# Etcha_Sketch.net
KiCad netlist of a schematic drawn in EAGLE
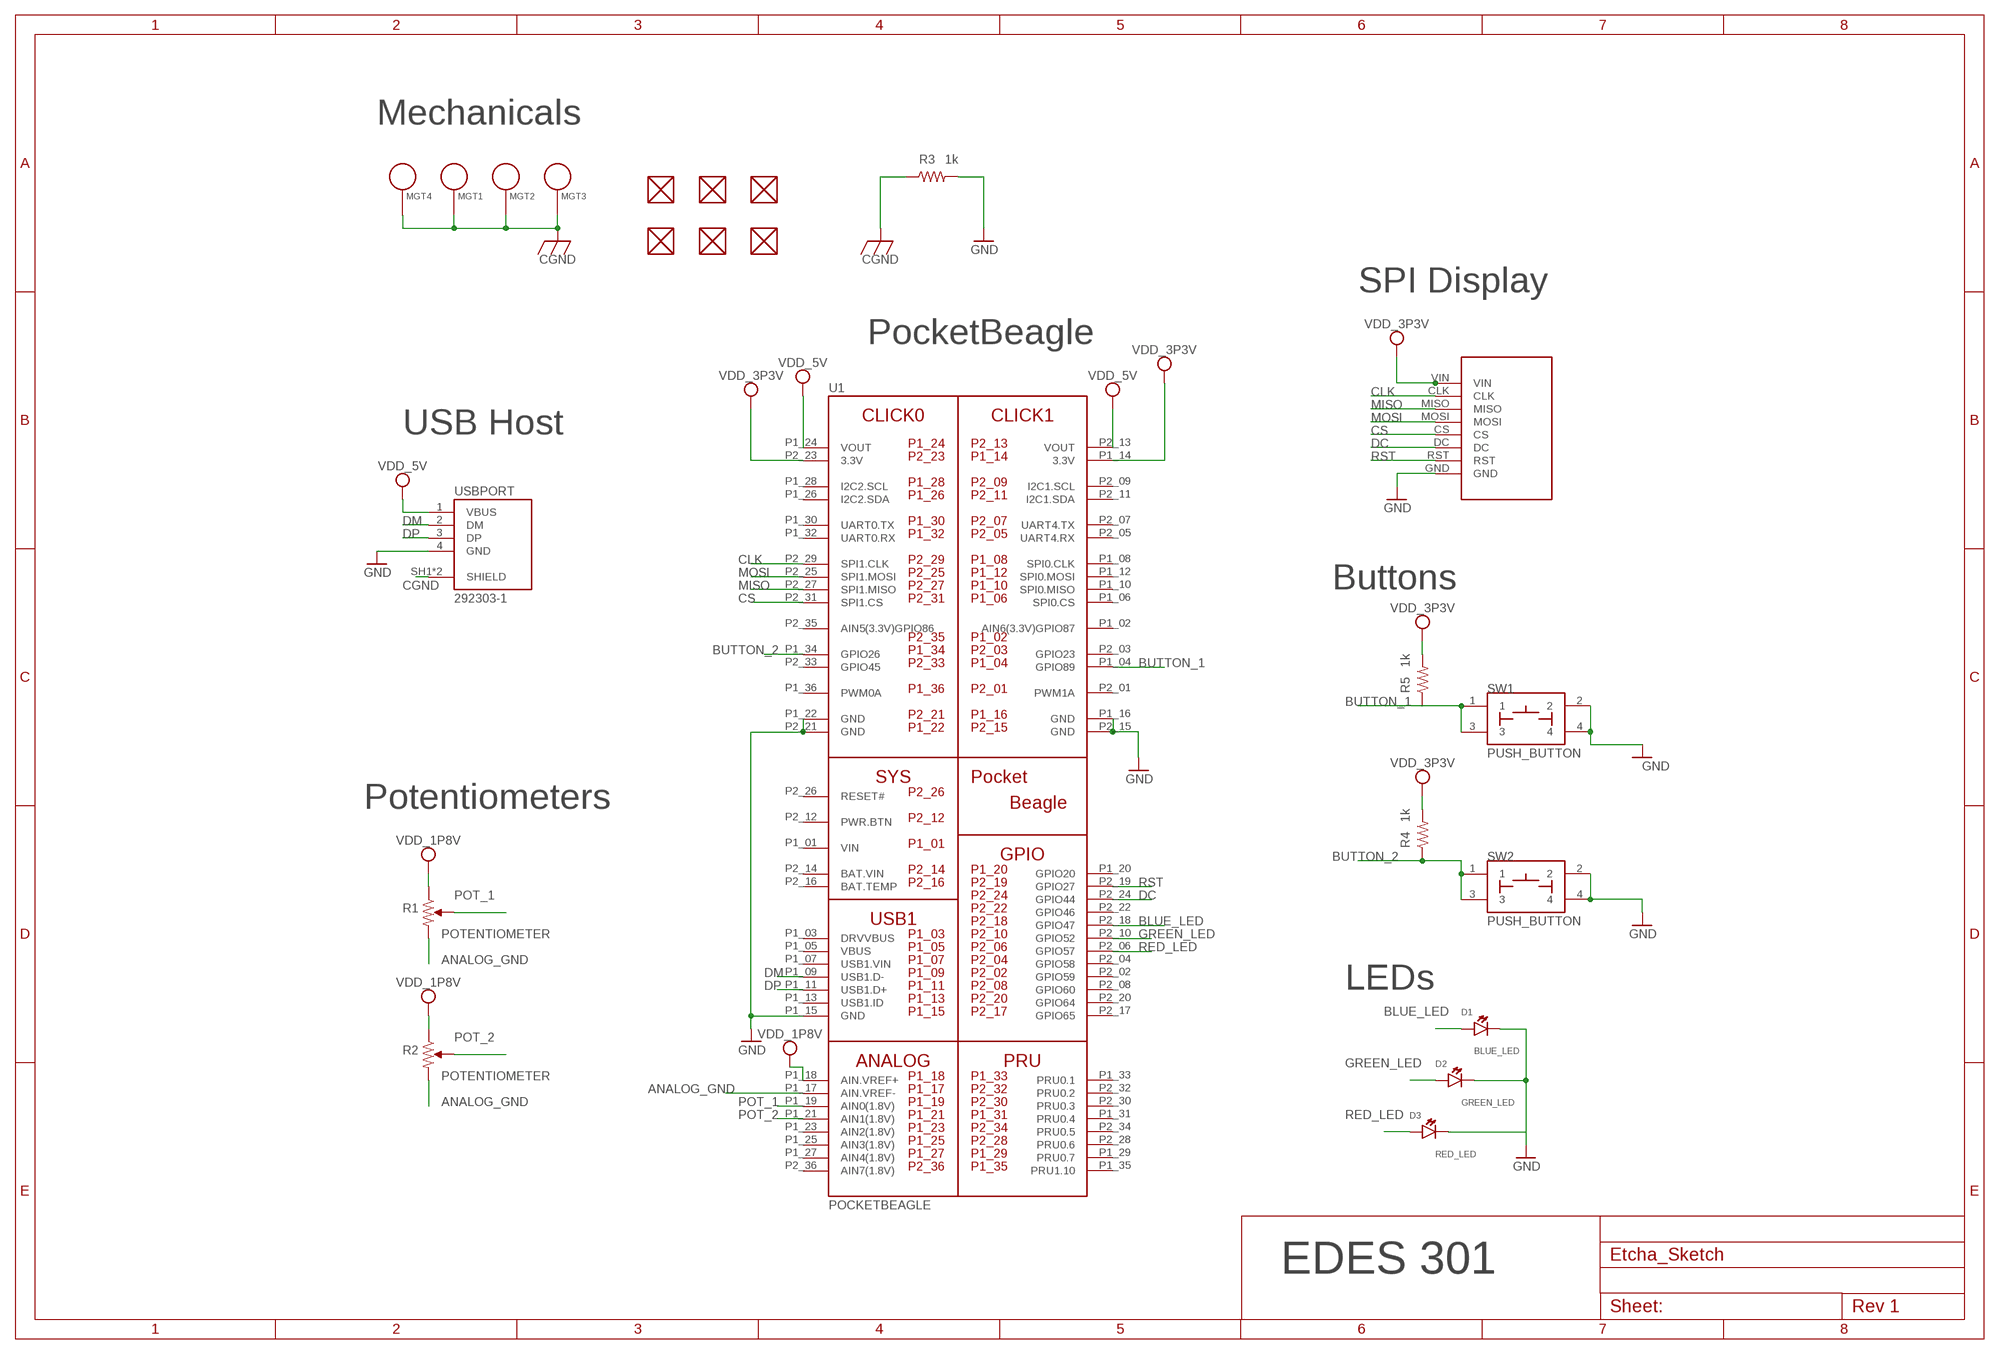
[diagram p0: schematic, sheet 1]

(export (version "E")
  (design (tool "Eeschema 10.0.6"))
  (components
    (comp (ref "D1")
      (value "BLUE_LED")
      (footprint "eagle-import:EIA-STD")
      (libsource (lib "eagle-import") (part "LED"))
    )
    (comp (ref "D2")
      (value "GREEN_LED")
      (footprint "eagle-import:EIA-STD")
      (libsource (lib "eagle-import") (part "LED"))
    )
    (comp (ref "D3")
      (value "RED_LED")
      (footprint "eagle-import:EIA-STD")
      (libsource (lib "eagle-import") (part "LED"))
    )
    (comp (ref "FUD1")
      (value "FIDUCIAL")
      (footprint "eagle-import:FIDUCIAL_40MIL")
      (libsource (lib "eagle-import") (part "FIDUCIAL"))
    )
    (comp (ref "FUD2")
      (value "FIDUCIAL")
      (footprint "eagle-import:FIDUCIAL_40MIL")
      (libsource (lib "eagle-import") (part "FIDUCIAL"))
    )
    (comp (ref "FUD3")
      (value "FIDUCIAL")
      (footprint "eagle-import:FIDUCIAL_40MIL")
      (libsource (lib "eagle-import") (part "FIDUCIAL"))
    )
    (comp (ref "FUD4")
      (value "FIDUCIAL")
      (footprint "eagle-import:FIDUCIAL_40MIL")
      (libsource (lib "eagle-import") (part "FIDUCIAL"))
    )
    (comp (ref "FUD5")
      (value "FIDUCIAL")
      (footprint "eagle-import:FIDUCIAL_40MIL")
      (libsource (lib "eagle-import") (part "FIDUCIAL"))
    )
    (comp (ref "FUD6")
      (value "FIDUCIAL")
      (footprint "eagle-import:FIDUCIAL_40MIL")
      (libsource (lib "eagle-import") (part "FIDUCIAL"))
    )
    (comp (ref "MGT1")
      (value "MOUNTING_HOLE")
      (footprint "eagle-import:MOUNTING_HOLE")
      (libsource (lib "eagle-import") (part "MOUNTING_HOLE"))
    )
    (comp (ref "MGT2")
      (value "MOUNTING_HOLE")
      (footprint "eagle-import:MOUNTING_HOLE")
      (libsource (lib "eagle-import") (part "MOUNTING_HOLE"))
    )
    (comp (ref "MGT3")
      (value "MOUNTING_HOLE")
      (footprint "eagle-import:MOUNTING_HOLE")
      (libsource (lib "eagle-import") (part "MOUNTING_HOLE"))
    )
    (comp (ref "MGT4")
      (value "MOUNTING_HOLE")
      (footprint "eagle-import:MOUNTING_HOLE")
      (libsource (lib "eagle-import") (part "MOUNTING_HOLE"))
    )
    (comp (ref "R1")
      (value "POTENTIOMETER")
      (footprint "eagle-import:POT-PO90S")
      (libsource (lib "eagle-import") (part "POTENTIOMETER"))
    )
    (comp (ref "R2")
      (value "POTENTIOMETER")
      (footprint "eagle-import:POT-PO90S")
      (libsource (lib "eagle-import") (part "POTENTIOMETER"))
    )
    (comp (ref "R3")
      (value "1k")
      (footprint "eagle-import:R0603")
      (libsource (lib "eagle-import") (part "R_R0603"))
    )
    (comp (ref "R4")
      (value "1k")
      (footprint "eagle-import:R0603")
      (libsource (lib "eagle-import") (part "R_R0603"))
    )
    (comp (ref "R5")
      (value "1k")
      (footprint "eagle-import:R0603")
      (libsource (lib "eagle-import") (part "R_R0603"))
    )
    (comp (ref "SPIDISPLAY")
      (value "SCREEN")
      (footprint "eagle-import:SCREEN")
      (libsource (lib "eagle-import") (part "SCREEN"))
    )
    (comp (ref "SW1")
      (value "PUSH_BUTTON")
      (footprint "eagle-import:BUTTON_12.5MM")
      (libsource (lib "eagle-import") (part "PUSH_BUTTON"))
    )
    (comp (ref "SW2")
      (value "PUSH_BUTTON")
      (footprint "eagle-import:BUTTON_12.5MM")
      (libsource (lib "eagle-import") (part "PUSH_BUTTON"))
    )
    (comp (ref "U1")
      (value "POCKETBEAGLE")
      (footprint "eagle-import:POCKETBEAGLE")
      (libsource (lib "eagle-import") (part "POCKETBEAGLE"))
    )
    (comp (ref "USBPORT")
      (value "292303-1")
      (footprint "eagle-import:TE_292303-1")
      (fields (field (name "MF") "TE Connectivity"))
      (libsource (lib "eagle-import") (part "292303-1"))
    )
  )
  (nets
    (net (code "1") (name "/ANALOG_GND") (class "Default")
      (node (ref "R1") (pin "CW") (pinfunction "CW_CW") (pintype "passive"))
      (node (ref "R2") (pin "CW") (pinfunction "CW_CW") (pintype "passive"))
      (node (ref "U1") (pin "P1_17") (pinfunction "AIN.VREF-_P1_17") (pintype "input"))
    )
    (net (code "2") (name "/BAT.VIN") (class "Default")
      (node (ref "U1") (pin "P2_14") (pinfunction "BAT.VIN_P2_14") (pintype "power_in"))
    )
    (net (code "3") (name "/BLUE_LED") (class "Default")
      (node (ref "D1") (pin "ANODE") (pinfunction "ANODE_ANODE") (pintype "bidirectional"))
      (node (ref "U1") (pin "P2_18") (pinfunction "GPIO47_P2_18") (pintype "bidirectional"))
    )
    (net (code "4") (name "/BUTTON_1") (class "Default")
      (node (ref "R5") (pin "1") (pinfunction "1_1") (pintype "passive"))
      (node (ref "SW1") (pin "1") (pinfunction "1_1") (pintype "bidirectional"))
      (node (ref "SW1") (pin "3") (pinfunction "3_3") (pintype "bidirectional"))
      (node (ref "U1") (pin "P1_04") (pinfunction "GPIO89_P1_04") (pintype "bidirectional"))
    )
    (net (code "5") (name "/BUTTON_2") (class "Default")
      (node (ref "R4") (pin "1") (pinfunction "1_1") (pintype "passive"))
      (node (ref "SW2") (pin "1") (pinfunction "1_1") (pintype "bidirectional"))
      (node (ref "SW2") (pin "3") (pinfunction "3_3") (pintype "bidirectional"))
      (node (ref "U1") (pin "P1_34") (pinfunction "GPIO26_P1_34") (pintype "bidirectional"))
    )
    (net (code "6") (name "/CLK") (class "Default")
      (node (ref "SPIDISPLAY") (pin "CLK") (pinfunction "CLK_CLK") (pintype "bidirectional"))
      (node (ref "U1") (pin "P2_29") (pinfunction "SPI1.CLK_P2_29") (pintype "bidirectional"))
    )
    (net (code "7") (name "/CS") (class "Default")
      (node (ref "SPIDISPLAY") (pin "CS") (pinfunction "CS_CS") (pintype "bidirectional"))
      (node (ref "U1") (pin "P2_31") (pinfunction "SPI1.CS_P2_31") (pintype "bidirectional"))
    )
    (net (code "8") (name "/DC") (class "Default")
      (node (ref "SPIDISPLAY") (pin "DC") (pinfunction "DC_DC") (pintype "bidirectional"))
      (node (ref "U1") (pin "P2_24") (pinfunction "GPIO44_P2_24") (pintype "bidirectional"))
    )
    (net (code "9") (name "/DM") (class "Default")
      (node (ref "U1") (pin "P1_09") (pinfunction "USB1.D-_P1_09") (pintype "bidirectional"))
      (node (ref "USBPORT") (pin "2") (pinfunction "DM_2") (pintype "passive"))
    )
    (net (code "10") (name "/DP") (class "Default")
      (node (ref "U1") (pin "P1_11") (pinfunction "USB1.D+_P1_11") (pintype "bidirectional"))
      (node (ref "USBPORT") (pin "3") (pinfunction "DP_3") (pintype "passive"))
    )
    (net (code "11") (name "/GREEN_LED") (class "Default")
      (node (ref "D2") (pin "ANODE") (pinfunction "ANODE_ANODE") (pintype "bidirectional"))
      (node (ref "U1") (pin "P2_10") (pinfunction "GPIO52_P2_10") (pintype "bidirectional"))
    )
    (net (code "12") (name "/MISO") (class "Default")
      (node (ref "SPIDISPLAY") (pin "MISO") (pinfunction "MISO_MISO") (pintype "bidirectional"))
      (node (ref "U1") (pin "P2_27") (pinfunction "SPI1.MISO_P2_27") (pintype "bidirectional"))
    )
    (net (code "13") (name "/MOSI") (class "Default")
      (node (ref "SPIDISPLAY") (pin "MOSI") (pinfunction "MOSI_MOSI") (pintype "bidirectional"))
      (node (ref "U1") (pin "P2_25") (pinfunction "SPI1.MOSI_P2_25") (pintype "bidirectional"))
    )
    (net (code "14") (name "/POT_1") (class "Default")
      (node (ref "R1") (pin "S") (pinfunction "S_S") (pintype "bidirectional"))
      (node (ref "U1") (pin "P1_19") (pinfunction "AIN0(1.8V)_P1_19") (pintype "input"))
    )
    (net (code "15") (name "/POT_2") (class "Default")
      (node (ref "R2") (pin "S") (pinfunction "S_S") (pintype "bidirectional"))
      (node (ref "U1") (pin "P1_21") (pinfunction "AIN1(1.8V)_P1_21") (pintype "input"))
    )
    (net (code "16") (name "/RED_LED") (class "Default")
      (node (ref "D3") (pin "ANODE") (pinfunction "ANODE_ANODE") (pintype "bidirectional"))
      (node (ref "U1") (pin "P2_06") (pinfunction "GPIO57_P2_06") (pintype "bidirectional"))
    )
    (net (code "17") (name "/RST") (class "Default")
      (node (ref "SPIDISPLAY") (pin "RST") (pinfunction "RST_RST") (pintype "bidirectional"))
      (node (ref "U1") (pin "P2_19") (pinfunction "GPIO27_P2_19") (pintype "bidirectional"))
    )
    (net (code "18") (name "/VIN") (class "Default")
      (node (ref "U1") (pin "P1_01") (pinfunction "VIN_P1_01") (pintype "power_in"))
    )
    (net (code "19") (name "CGND") (class "Default")
      (node (ref "MGT1") (pin "P$1") (pinfunction "P$1_P$1") (pintype "bidirectional"))
      (node (ref "MGT2") (pin "P$1") (pinfunction "P$1_P$1") (pintype "bidirectional"))
      (node (ref "MGT3") (pin "P$1") (pinfunction "P$1_P$1") (pintype "bidirectional"))
      (node (ref "MGT4") (pin "P$1") (pinfunction "P$1_P$1") (pintype "bidirectional"))
      (node (ref "R3") (pin "1") (pinfunction "1_1") (pintype "passive"))
      (node (ref "USBPORT") (pin "SH1") (pinfunction "SHIELD_SH1") (pintype "passive"))
      (node (ref "USBPORT") (pin "SH2") (pinfunction "SHIELD_SH2") (pintype "passive"))
    )
    (net (code "20") (name "GND") (class "Default")
      (node (ref "D1") (pin "CATHODE") (pinfunction "CATHODE_CATHODE") (pintype "bidirectional"))
      (node (ref "D2") (pin "CATHODE") (pinfunction "CATHODE_CATHODE") (pintype "bidirectional"))
      (node (ref "R3") (pin "2") (pinfunction "2_2") (pintype "passive"))
      (node (ref "SPIDISPLAY") (pin "GND") (pinfunction "GND_GND") (pintype "bidirectional"))
      (node (ref "SW1") (pin "2") (pinfunction "2_2") (pintype "bidirectional"))
      (node (ref "SW1") (pin "4") (pinfunction "4_4") (pintype "bidirectional"))
      (node (ref "SW2") (pin "2") (pinfunction "2_2") (pintype "bidirectional"))
      (node (ref "SW2") (pin "4") (pinfunction "4_4") (pintype "bidirectional"))
      (node (ref "U1") (pin "P1_15") (pinfunction "GND_P1_15") (pintype "bidirectional"))
      (node (ref "U1") (pin "P1_16") (pinfunction "GND_P1_16") (pintype "power_in"))
      (node (ref "U1") (pin "P1_22") (pinfunction "GND_P1_22") (pintype "power_in"))
      (node (ref "U1") (pin "P2_15") (pinfunction "GND_P2_15") (pintype "power_in"))
      (node (ref "U1") (pin "P2_21") (pinfunction "GND_P2_21") (pintype "power_in"))
      (node (ref "USBPORT") (pin "4") (pinfunction "GND_4") (pintype "passive"))
    )
    (net (code "21") (name "VDD_1P8V") (class "Default")
      (node (ref "R1") (pin "CCW") (pinfunction "CCW_CCW") (pintype "passive"))
      (node (ref "R2") (pin "CCW") (pinfunction "CCW_CCW") (pintype "passive"))
      (node (ref "U1") (pin "P1_18") (pinfunction "AIN.VREF+_P1_18") (pintype "input"))
    )
    (net (code "22") (name "VDD_3P3V") (class "Default")
      (node (ref "R4") (pin "2") (pinfunction "2_2") (pintype "passive"))
      (node (ref "R5") (pin "2") (pinfunction "2_2") (pintype "passive"))
      (node (ref "SPIDISPLAY") (pin "VIN") (pinfunction "VIN_VIN") (pintype "bidirectional"))
      (node (ref "U1") (pin "P1_14") (pinfunction "3.3V_P1_14") (pintype "power_in"))
      (node (ref "U1") (pin "P2_23") (pinfunction "3.3V_P2_23") (pintype "power_in"))
    )
    (net (code "23") (name "VDD_5V") (class "Default")
      (node (ref "U1") (pin "P1_24") (pinfunction "VOUT_P1_24") (pintype "power_in"))
      (node (ref "U1") (pin "P2_13") (pinfunction "VOUT_P2_13") (pintype "power_in"))
      (node (ref "USBPORT") (pin "1") (pinfunction "VBUS_1") (pintype "passive"))
    )
    (net (code "24") (name "unconnected-(D3-PadCATHODE)") (class "Default")
      (node (ref "D3") (pin "CATHODE") (pinfunction "CATHODE_CATHODE") (pintype "bidirectional"))
    )
    (net (code "25") (name "unconnected-(FUD1-PadP$1)") (class "Default")
      (node (ref "FUD1") (pin "P$1") (pinfunction "P$1_P$1") (pintype "no_connect"))
    )
    (net (code "26") (name "unconnected-(FUD2-PadP$1)") (class "Default")
      (node (ref "FUD2") (pin "P$1") (pinfunction "P$1_P$1") (pintype "no_connect"))
    )
    (net (code "27") (name "unconnected-(FUD3-PadP$1)") (class "Default")
      (node (ref "FUD3") (pin "P$1") (pinfunction "P$1_P$1") (pintype "no_connect"))
    )
    (net (code "28") (name "unconnected-(FUD4-PadP$1)") (class "Default")
      (node (ref "FUD4") (pin "P$1") (pinfunction "P$1_P$1") (pintype "no_connect"))
    )
    (net (code "29") (name "unconnected-(FUD5-PadP$1)") (class "Default")
      (node (ref "FUD5") (pin "P$1") (pinfunction "P$1_P$1") (pintype "no_connect"))
    )
    (net (code "30") (name "unconnected-(FUD6-PadP$1)") (class "Default")
      (node (ref "FUD6") (pin "P$1") (pinfunction "P$1_P$1") (pintype "no_connect"))
    )
    (net (code "31") (name "unconnected-(U1-AIN2(1.8V)-PadP1_23)") (class "Default")
      (node (ref "U1") (pin "P1_23") (pinfunction "AIN2(1.8V)_P1_23") (pintype "input"))
    )
    (net (code "32") (name "unconnected-(U1-AIN3(1.8V)-PadP1_25)") (class "Default")
      (node (ref "U1") (pin "P1_25") (pinfunction "AIN3(1.8V)_P1_25") (pintype "input"))
    )
    (net (code "33") (name "unconnected-(U1-AIN4(1.8V)-PadP1_27)") (class "Default")
      (node (ref "U1") (pin "P1_27") (pinfunction "AIN4(1.8V)_P1_27") (pintype "input"))
    )
    (net (code "34") (name "unconnected-(U1-AIN5(3.3V)GPIO86-PadP2_35)") (class "Default")
      (node (ref "U1") (pin "P2_35") (pinfunction "AIN5(3.3V)GPIO86_P2_35") (pintype "bidirectional"))
    )
    (net (code "35") (name "unconnected-(U1-AIN6(3.3V)GPIO87-PadP1_02)") (class "Default")
      (node (ref "U1") (pin "P1_02") (pinfunction "AIN6(3.3V)GPIO87_P1_02") (pintype "bidirectional"))
    )
    (net (code "36") (name "unconnected-(U1-AIN7(1.8V)-PadP2_36)") (class "Default")
      (node (ref "U1") (pin "P2_36") (pinfunction "AIN7(1.8V)_P2_36") (pintype "input"))
    )
    (net (code "37") (name "unconnected-(U1-BAT.TEMP-PadP2_16)") (class "Default")
      (node (ref "U1") (pin "P2_16") (pinfunction "BAT.TEMP_P2_16") (pintype "input"))
    )
    (net (code "38") (name "unconnected-(U1-DRVVBUS-PadP1_03)") (class "Default")
      (node (ref "U1") (pin "P1_03") (pinfunction "DRVVBUS_P1_03") (pintype "bidirectional"))
    )
    (net (code "39") (name "unconnected-(U1-GPIO20-PadP1_20)") (class "Default")
      (node (ref "U1") (pin "P1_20") (pinfunction "GPIO20_P1_20") (pintype "bidirectional"))
    )
    (net (code "40") (name "unconnected-(U1-GPIO23-PadP2_03)") (class "Default")
      (node (ref "U1") (pin "P2_03") (pinfunction "GPIO23_P2_03") (pintype "bidirectional"))
    )
    (net (code "41") (name "unconnected-(U1-GPIO45-PadP2_33)") (class "Default")
      (node (ref "U1") (pin "P2_33") (pinfunction "GPIO45_P2_33") (pintype "bidirectional"))
    )
    (net (code "42") (name "unconnected-(U1-GPIO46-PadP2_22)") (class "Default")
      (node (ref "U1") (pin "P2_22") (pinfunction "GPIO46_P2_22") (pintype "bidirectional"))
    )
    (net (code "43") (name "unconnected-(U1-GPIO58-PadP2_04)") (class "Default")
      (node (ref "U1") (pin "P2_04") (pinfunction "GPIO58_P2_04") (pintype "bidirectional"))
    )
    (net (code "44") (name "unconnected-(U1-GPIO59-PadP2_02)") (class "Default")
      (node (ref "U1") (pin "P2_02") (pinfunction "GPIO59_P2_02") (pintype "bidirectional"))
    )
    (net (code "45") (name "unconnected-(U1-GPIO60-PadP2_08)") (class "Default")
      (node (ref "U1") (pin "P2_08") (pinfunction "GPIO60_P2_08") (pintype "bidirectional"))
    )
    (net (code "46") (name "unconnected-(U1-GPIO64-PadP2_20)") (class "Default")
      (node (ref "U1") (pin "P2_20") (pinfunction "GPIO64_P2_20") (pintype "bidirectional"))
    )
    (net (code "47") (name "unconnected-(U1-GPIO65-PadP2_17)") (class "Default")
      (node (ref "U1") (pin "P2_17") (pinfunction "GPIO65_P2_17") (pintype "bidirectional"))
    )
    (net (code "48") (name "unconnected-(U1-I2C1.SCL-PadP2_09)") (class "Default")
      (node (ref "U1") (pin "P2_09") (pinfunction "I2C1.SCL_P2_09") (pintype "bidirectional"))
    )
    (net (code "49") (name "unconnected-(U1-I2C1.SDA-PadP2_11)") (class "Default")
      (node (ref "U1") (pin "P2_11") (pinfunction "I2C1.SDA_P2_11") (pintype "bidirectional"))
    )
    (net (code "50") (name "unconnected-(U1-I2C2.SCL-PadP1_28)") (class "Default")
      (node (ref "U1") (pin "P1_28") (pinfunction "I2C2.SCL_P1_28") (pintype "bidirectional"))
    )
    (net (code "51") (name "unconnected-(U1-I2C2.SDA-PadP1_26)") (class "Default")
      (node (ref "U1") (pin "P1_26") (pinfunction "I2C2.SDA_P1_26") (pintype "bidirectional"))
    )
    (net (code "52") (name "unconnected-(U1-PRU0.1-PadP1_33)") (class "Default")
      (node (ref "U1") (pin "P1_33") (pinfunction "PRU0.1_P1_33") (pintype "bidirectional"))
    )
    (net (code "53") (name "unconnected-(U1-PRU0.2-PadP2_32)") (class "Default")
      (node (ref "U1") (pin "P2_32") (pinfunction "PRU0.2_P2_32") (pintype "bidirectional"))
    )
    (net (code "54") (name "unconnected-(U1-PRU0.3-PadP2_30)") (class "Default")
      (node (ref "U1") (pin "P2_30") (pinfunction "PRU0.3_P2_30") (pintype "bidirectional"))
    )
    (net (code "55") (name "unconnected-(U1-PRU0.4-PadP1_31)") (class "Default")
      (node (ref "U1") (pin "P1_31") (pinfunction "PRU0.4_P1_31") (pintype "bidirectional"))
    )
    (net (code "56") (name "unconnected-(U1-PRU0.5-PadP2_34)") (class "Default")
      (node (ref "U1") (pin "P2_34") (pinfunction "PRU0.5_P2_34") (pintype "bidirectional"))
    )
    (net (code "57") (name "unconnected-(U1-PRU0.6-PadP2_28)") (class "Default")
      (node (ref "U1") (pin "P2_28") (pinfunction "PRU0.6_P2_28") (pintype "bidirectional"))
    )
    (net (code "58") (name "unconnected-(U1-PRU0.7-PadP1_29)") (class "Default")
      (node (ref "U1") (pin "P1_29") (pinfunction "PRU0.7_P1_29") (pintype "bidirectional"))
    )
    (net (code "59") (name "unconnected-(U1-PRU1.10-PadP1_35)") (class "Default")
      (node (ref "U1") (pin "P1_35") (pinfunction "PRU1.10_P1_35") (pintype "bidirectional"))
    )
    (net (code "60") (name "unconnected-(U1-PWM0A-PadP1_36)") (class "Default")
      (node (ref "U1") (pin "P1_36") (pinfunction "PWM0A_P1_36") (pintype "bidirectional"))
    )
    (net (code "61") (name "unconnected-(U1-PWM1A-PadP2_01)") (class "Default")
      (node (ref "U1") (pin "P2_01") (pinfunction "PWM1A_P2_01") (pintype "bidirectional"))
    )
    (net (code "62") (name "unconnected-(U1-PWR.BTN-PadP2_12)") (class "Default")
      (node (ref "U1") (pin "P2_12") (pinfunction "PWR.BTN_P2_12") (pintype "input"))
    )
    (net (code "63") (name "unconnected-(U1-RESET#-PadP2_26)") (class "Default")
      (node (ref "U1") (pin "P2_26") (pinfunction "RESET#_P2_26") (pintype "input"))
    )
    (net (code "64") (name "unconnected-(U1-SPI0.CLK-PadP1_08)") (class "Default")
      (node (ref "U1") (pin "P1_08") (pinfunction "SPI0.CLK_P1_08") (pintype "bidirectional"))
    )
    (net (code "65") (name "unconnected-(U1-SPI0.CS-PadP1_06)") (class "Default")
      (node (ref "U1") (pin "P1_06") (pinfunction "SPI0.CS_P1_06") (pintype "bidirectional"))
    )
    (net (code "66") (name "unconnected-(U1-SPI0.MISO-PadP1_10)") (class "Default")
      (node (ref "U1") (pin "P1_10") (pinfunction "SPI0.MISO_P1_10") (pintype "bidirectional"))
    )
    (net (code "67") (name "unconnected-(U1-SPI0.MOSI-PadP1_12)") (class "Default")
      (node (ref "U1") (pin "P1_12") (pinfunction "SPI0.MOSI_P1_12") (pintype "bidirectional"))
    )
    (net (code "68") (name "unconnected-(U1-UART0.RX-PadP1_32)") (class "Default")
      (node (ref "U1") (pin "P1_32") (pinfunction "UART0.RX_P1_32") (pintype "bidirectional"))
    )
    (net (code "69") (name "unconnected-(U1-UART0.TX-PadP1_30)") (class "Default")
      (node (ref "U1") (pin "P1_30") (pinfunction "UART0.TX_P1_30") (pintype "bidirectional"))
    )
    (net (code "70") (name "unconnected-(U1-UART4.RX-PadP2_05)") (class "Default")
      (node (ref "U1") (pin "P2_05") (pinfunction "UART4.RX_P2_05") (pintype "bidirectional"))
    )
    (net (code "71") (name "unconnected-(U1-UART4.TX-PadP2_07)") (class "Default")
      (node (ref "U1") (pin "P2_07") (pinfunction "UART4.TX_P2_07") (pintype "bidirectional"))
    )
    (net (code "72") (name "unconnected-(U1-USB1.ID-PadP1_13)") (class "Default")
      (node (ref "U1") (pin "P1_13") (pinfunction "USB1.ID_P1_13") (pintype "bidirectional"))
    )
    (net (code "73") (name "unconnected-(U1-USB1.VIN-PadP1_07)") (class "Default")
      (node (ref "U1") (pin "P1_07") (pinfunction "USB1.VIN_P1_07") (pintype "bidirectional"))
    )
    (net (code "74") (name "unconnected-(U1-VBUS-PadP1_05)") (class "Default")
      (node (ref "U1") (pin "P1_05") (pinfunction "VBUS_P1_05") (pintype "bidirectional"))
    )
  )
)
